# STM32F429_minimum_system.net
KiCad netlist of a schematic drawn in Altium Designer
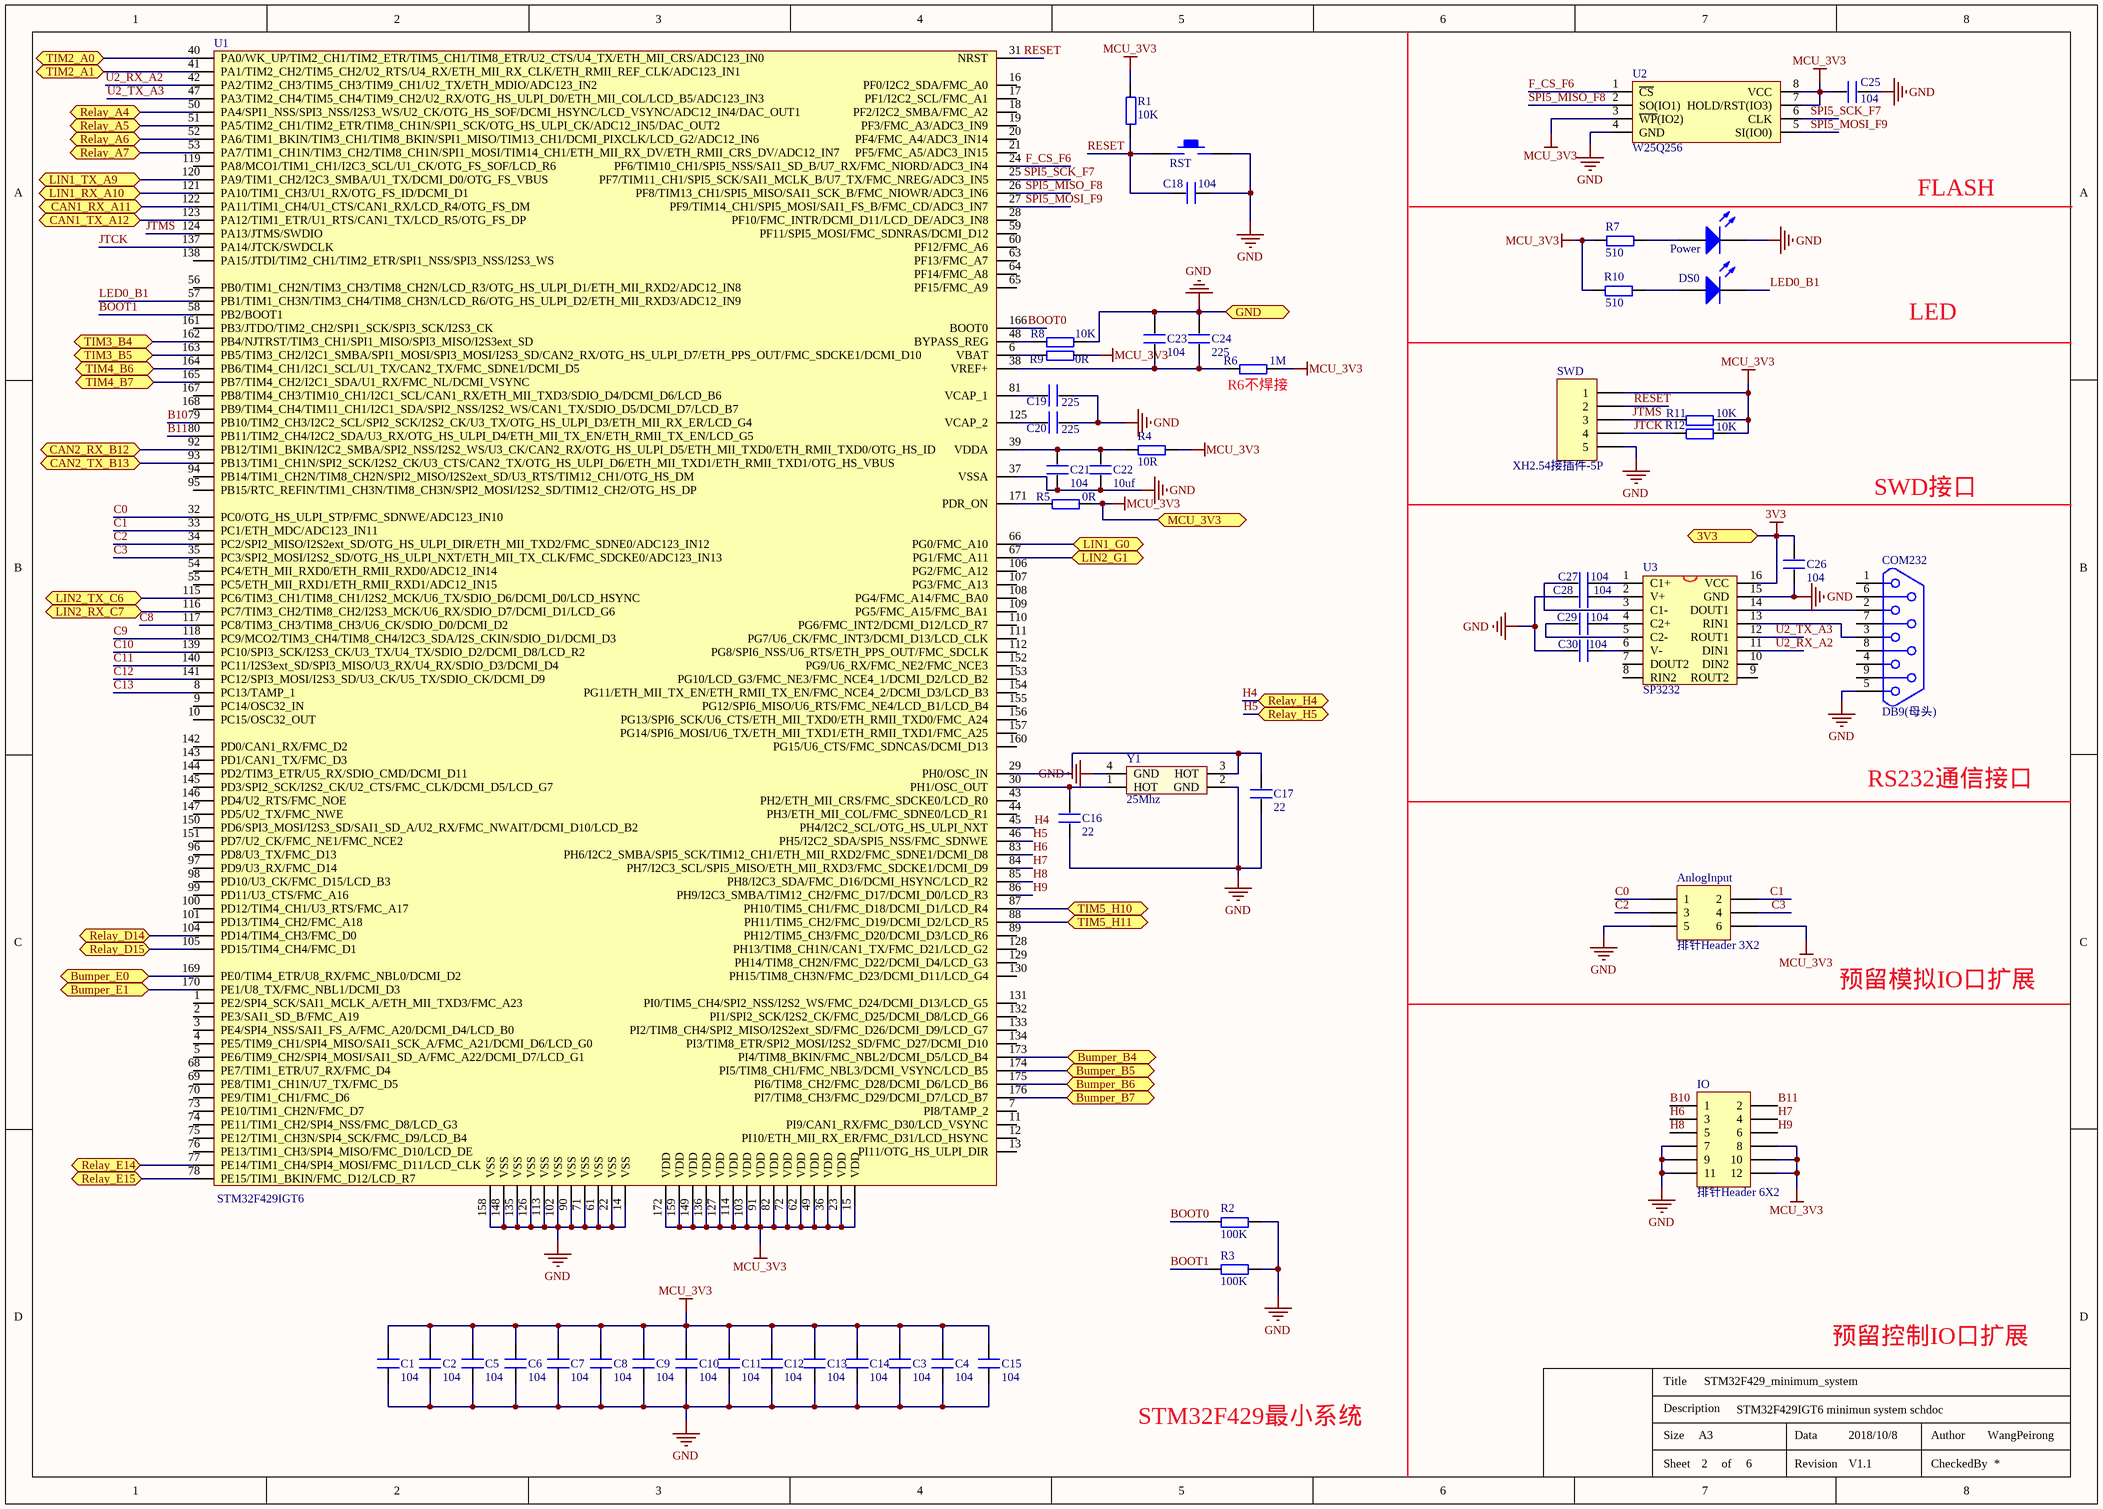
[diagram p0: STM32F429_minimum_system.SchDoc]

(export (version "E")
  (design (tool "Eeschema 10.0.6"))
  (components
    (comp (ref "AnlogInput")
      (value "排针Header 3X2")
      (footprint "F-HEADER-2*3-2.54MM")
      (description "Header, 3-Pin, Dual row")
      (fields (field (name "PUBLISHER") "Altium Limited"))
      (libsource (lib "接插件集成库") (part "Header 3X2"))
    )
    (comp (ref "C1") (value "104") (footprint "0603P") (libsource (lib "阿波罗STM32F4&F7底板封装库") (part "C")))
    (comp (ref "C2") (value "104") (footprint "0603P") (libsource (lib "阿波罗STM32F4&F7底板封装库") (part "C")))
    (comp (ref "C3") (value "104") (footprint "0603P") (libsource (lib "阿波罗STM32F4&F7底板封装库") (part "C")))
    (comp (ref "C4") (value "104") (footprint "0603P") (libsource (lib "阿波罗STM32F4&F7底板封装库") (part "C")))
    (comp (ref "C5") (value "104") (footprint "0603P") (libsource (lib "阿波罗STM32F4&F7底板封装库") (part "C")))
    (comp (ref "C6") (value "104") (footprint "0603P") (libsource (lib "阿波罗STM32F4&F7底板封装库") (part "C")))
    (comp (ref "C7") (value "104") (footprint "0603P") (libsource (lib "阿波罗STM32F4&F7底板封装库") (part "C")))
    (comp (ref "C8") (value "104") (footprint "0603P") (libsource (lib "阿波罗STM32F4&F7底板封装库") (part "C")))
    (comp (ref "C9") (value "104") (footprint "0603P") (libsource (lib "阿波罗STM32F4&F7底板封装库") (part "C")))
    (comp (ref "C10") (value "104") (footprint "0603P") (libsource (lib "阿波罗STM32F4&F7底板封装库") (part "C")))
    (comp (ref "C11") (value "104") (footprint "0603P") (libsource (lib "阿波罗STM32F4&F7底板封装库") (part "C")))
    (comp (ref "C12") (value "104") (footprint "0603P") (libsource (lib "阿波罗STM32F4&F7底板封装库") (part "C")))
    (comp (ref "C13") (value "104") (footprint "0603P") (libsource (lib "阿波罗STM32F4&F7底板封装库") (part "C")))
    (comp (ref "C14") (value "104") (footprint "0603P") (libsource (lib "阿波罗STM32F4&F7底板封装库") (part "C")))
    (comp (ref "C15") (value "104") (footprint "0603P") (libsource (lib "阿波罗STM32F4&F7底板封装库") (part "C")))
    (comp (ref "C16") (value "22") (footprint "0603P") (libsource (lib "阿波罗STM32F4&F7底板封装库") (part "C")))
    (comp (ref "C17") (value "22") (footprint "0603P") (libsource (lib "阿波罗STM32F4&F7底板封装库") (part "C")))
    (comp (ref "C18") (value "104") (footprint "0603P") (libsource (lib "阿波罗STM32F4&F7底板封装库") (part "C")))
    (comp (ref "C19") (value "225") (footprint "0603P") (libsource (lib "阿波罗STM32F4&F7底板封装库") (part "C")))
    (comp (ref "C20") (value "225") (footprint "0603P") (libsource (lib "阿波罗STM32F4&F7底板封装库") (part "C")))
    (comp (ref "C21") (value "104") (footprint "0603P") (libsource (lib "阿波罗STM32F4&F7底板封装库") (part "C")))
    (comp (ref "C22") (value "10uf") (footprint "0603P") (libsource (lib "阿波罗STM32F4&F7底板封装库") (part "C")))
    (comp (ref "C23") (value "104") (footprint "0603P") (libsource (lib "阿波罗STM32F4&F7底板封装库") (part "C")))
    (comp (ref "C24") (value "225") (footprint "0603P") (libsource (lib "阿波罗STM32F4&F7底板封装库") (part "C")))
    (comp (ref "C25") (value "104") (footprint "0603P") (libsource (lib "阿波罗STM32F4&F7底板封装库") (part "C")))
    (comp (ref "C26") (value "104") (footprint "0603P") (libsource (lib "STM32F767核心板封装库") (part "C")))
    (comp (ref "C27") (value "104") (footprint "0603P") (libsource (lib "STM32F767核心板封装库") (part "C")))
    (comp (ref "C28") (value "104") (footprint "0603P") (libsource (lib "STM32F767核心板封装库") (part "C")))
    (comp (ref "C29") (value "104") (footprint "0603P") (libsource (lib "STM32F767核心板封装库") (part "C")))
    (comp (ref "C30") (value "104") (footprint "0603P") (libsource (lib "STM32F767核心板封装库") (part "C")))
    (comp (ref "COM232")
      (value "DB9(母头)")
      (footprint "DB9")
      (libsource (lib "阿波罗STM32F4&F7底板封装库") (part "DB9"))
    )
    (comp (ref "DS0")
      (value "LED绿色")
      (footprint "SMDLED")
      (description "Typical RED, GREEN, YELLOW, AMBER GaAs LED")
      (fields (field (name "PUBLISHER") "Altium Limited"))
      (libsource (lib "阿波罗STM32F4&F7底板封装库") (part "LED2"))
    )
    (comp (ref "IO")
      (value "排针Header 6X2")
      (footprint "F-HEADER-2*6-2.54MM")
      (description "Header, 6-Pin, Dual row")
      (fields (field (name "PUBLISHER") "Altium Limited"))
      (libsource (lib "接插件集成库") (part "Header 6X2"))
    )
    (comp (ref "Power")
      (value "LED红色")
      (footprint "SMDLED")
      (description "Typical RED, GREEN, YELLOW, AMBER GaAs LED")
      (fields (field (name "PUBLISHER") "Altium Limited"))
      (libsource (lib "阿波罗STM32F4&F7底板封装库") (part "LED2"))
    )
    (comp (ref "R1") (value "10K") (footprint "0603P") (libsource (lib "STM32F429核心板封装库") (part "R")))
    (comp (ref "R2") (value "100K") (footprint "0603P") (libsource (lib "STM32F429核心板封装库") (part "R")))
    (comp (ref "R3") (value "100K") (footprint "0603P") (libsource (lib "STM32F429核心板封装库") (part "R")))
    (comp (ref "R4") (value "10R") (footprint "0603P") (libsource (lib "STM32F429核心板封装库") (part "R")))
    (comp (ref "R5") (value "0R") (footprint "0603P") (libsource (lib "STM32F429核心板封装库") (part "R")))
    (comp (ref "R6") (value "1M") (footprint "0603P") (libsource (lib "STM32F429核心板封装库") (part "R")))
    (comp (ref "R7") (value "510") (footprint "0603P") (libsource (lib "STM32F429核心板封装库") (part "R")))
    (comp (ref "R8") (value "10K") (footprint "0603P") (libsource (lib "STM32F429核心板封装库") (part "R")))
    (comp (ref "R9") (value "0R") (footprint "0603P") (libsource (lib "STM32F429核心板封装库") (part "R")))
    (comp (ref "R10") (value "510") (footprint "0603P") (libsource (lib "STM32F429核心板封装库") (part "R")))
    (comp (ref "R11") (value "10K") (footprint "0603P") (libsource (lib "STM32F429核心板封装库") (part "R")))
    (comp (ref "R12") (value "10K") (footprint "0603P") (libsource (lib "STM32F429核心板封装库") (part "R")))
    (comp (ref "RST")
      (value "KEY_M")
      (footprint "KEY_SOP3625")
      (libsource (lib "STM32F429核心板封装库") (part "KEY_M"))
    )
    (comp (ref "SWD")
      (value "XH2.54接插件-5P")
      (footprint "F-HEADER-5-2.54MM")
      (description "Header, 5-Pin")
      (fields (field (name "PUBLISHER") "Altium Limited"))
      (libsource (lib "接插件集成库") (part "Header 5"))
    )
    (comp (ref "U1")
      (value "STM32F429IGT6")
      (footprint "LQFP176")
      (libsource (lib "STM32F429核心板封装库") (part "STM32F429IGT6"))
    )
    (comp (ref "U2")
      (value "W25Q256")
      (footprint "WSON8")
      (description "W25Q128")
      (libsource (lib "STM32F429核心板封装库") (part "W25Q128"))
    )
    (comp (ref "U3")
      (value "SP3232")
      (footprint "SOP16M")
      (libsource (lib "阿波罗STM32F4&F7底板封装库") (part "MAX3232"))
    )
    (comp (ref "Y1")
      (value "25Mhz")
      (footprint "XTAL3225")
      (description "3225贴片无源晶振")
      (libsource (lib "STM32F429核心板封装库") (part "XTAL_3225"))
    )
  )
  (nets
    (net (code "1") (name "/B10") (class "Default")
      (node (ref "IO") (pin "1") (pinfunction "1_1") (pintype "passive"))
      (node (ref "U1") (pin "79") (pinfunction "PB10/TIM2_CH3/I2C2_SCL/SPI2_SCK/I2S2_CK/U3_TX/OTG_HS_ULPI_D3/ETH_MII_RX_ER/LCD_G4_79") (pintype "passive"))
    )
    (net (code "2") (name "/B11") (class "Default")
      (node (ref "IO") (pin "2") (pinfunction "2_2") (pintype "passive"))
      (node (ref "U1") (pin "80") (pinfunction "PB11/TIM2_CH4/I2C2_SDA/U3_RX/OTG_HS_ULPI_D4/ETH_MII_TX_EN/ETH_RMII_TX_EN/LCD_G5_80") (pintype "passive"))
    )
    (net (code "3") (name "/BOOT0") (class "Default")
      (node (ref "R2") (pin "1") (pintype "passive"))
      (node (ref "U1") (pin "166") (pinfunction "BOOT0_166") (pintype "passive"))
    )
    (net (code "4") (name "/BOOT1") (class "Default")
      (node (ref "R3") (pin "1") (pintype "passive"))
      (node (ref "U1") (pin "58") (pinfunction "PB2/BOOT1_58") (pintype "passive"))
    )
    (net (code "5") (name "/Bumper_B4") (class "Default")
      (node (ref "U1") (pin "173") (pinfunction "PI4/TIM8_BKIN/FMC_NBL2/DCMI_D5/LCD_B4_173") (pintype "passive"))
    )
    (net (code "6") (name "/Bumper_B5") (class "Default")
      (node (ref "U1") (pin "174") (pinfunction "PI5/TIM8_CH1/FMC_NBL3/DCMI_VSYNC/LCD_B5_174") (pintype "passive"))
    )
    (net (code "7") (name "/Bumper_B6") (class "Default")
      (node (ref "U1") (pin "175") (pinfunction "PI6/TIM8_CH2/FMC_D28/DCMI_D6/LCD_B6_175") (pintype "passive"))
    )
    (net (code "8") (name "/Bumper_B7") (class "Default")
      (node (ref "U1") (pin "176") (pinfunction "PI7/TIM8_CH3/FMC_D29/DCMI_D7/LCD_B7_176") (pintype "passive"))
    )
    (net (code "9") (name "/Bumper_E0") (class "Default")
      (node (ref "U1") (pin "169") (pinfunction "PE0/TIM4_ETR/U8_RX/FMC_NBL0/DCMI_D2_169") (pintype "passive"))
    )
    (net (code "10") (name "/Bumper_E1") (class "Default")
      (node (ref "U1") (pin "170") (pinfunction "PE1/U8_TX/FMC_NBL1/DCMI_D3_170") (pintype "passive"))
    )
    (net (code "11") (name "/C0") (class "Default")
      (node (ref "AnlogInput") (pin "1") (pinfunction "1_1") (pintype "passive"))
      (node (ref "U1") (pin "32") (pinfunction "PC0/OTG_HS_ULPI_STP/FMC_SDNWE/ADC123_IN10_32") (pintype "passive"))
    )
    (net (code "12") (name "/C1") (class "Default")
      (node (ref "AnlogInput") (pin "2") (pinfunction "2_2") (pintype "passive"))
      (node (ref "U1") (pin "33") (pinfunction "PC1/ETH_MDC/ADC123_IN11_33") (pintype "passive"))
    )
    (net (code "13") (name "/C2") (class "Default")
      (node (ref "AnlogInput") (pin "3") (pinfunction "3_3") (pintype "passive"))
      (node (ref "U1") (pin "34") (pinfunction "PC2/SPI2_MISO/I2S2ext_SD/OTG_HS_ULPI_DIR/ETH_MII_TXD2/FMC_SDNE0/ADC123_IN12_34") (pintype "passive"))
    )
    (net (code "14") (name "/C3") (class "Default")
      (node (ref "AnlogInput") (pin "4") (pinfunction "4_4") (pintype "passive"))
      (node (ref "U1") (pin "35") (pinfunction "PC3/SPI2_MOSI/I2S2_SD/OTG_HS_ULPI_NXT/ETH_MII_TX_CLK/FMC_SDCKE0/ADC123_IN13_35") (pintype "passive"))
    )
    (net (code "15") (name "/C8") (class "Default")
      (node (ref "U1") (pin "117") (pinfunction "PC8/TIM3_CH3/TIM8_CH3/U6_CK/SDIO_D0/DCMI_D2_117") (pintype "passive"))
    )
    (net (code "16") (name "/C9") (class "Default")
      (node (ref "U1") (pin "118") (pinfunction "PC9/MCO2/TIM3_CH4/TIM8_CH4/I2C3_SDA/I2S_CKIN/SDIO_D1/DCMI_D3_118") (pintype "passive"))
    )
    (net (code "17") (name "/C10") (class "Default")
      (node (ref "U1") (pin "139") (pinfunction "PC10/SPI3_SCK/I2S3_CK/U3_TX/U4_TX/SDIO_D2/DCMI_D8/LCD_R2_139") (pintype "passive"))
    )
    (net (code "18") (name "/C11") (class "Default")
      (node (ref "U1") (pin "140") (pinfunction "PC11/I2S3ext_SD/SPI3_MISO/U3_RX/U4_RX/SDIO_D3/DCMI_D4_140") (pintype "passive"))
    )
    (net (code "19") (name "/C12") (class "Default")
      (node (ref "U1") (pin "141") (pinfunction "PC12/SPI3_MOSI/I2S3_SD/U3_CK/U5_TX/SDIO_CK/DCMI_D9_141") (pintype "passive"))
    )
    (net (code "20") (name "/C13") (class "Default")
      (node (ref "U1") (pin "8") (pinfunction "PC13/TAMP_1_8") (pintype "passive"))
    )
    (net (code "21") (name "/CAN1_RX_A11") (class "Default")
      (node (ref "U1") (pin "122") (pinfunction "PA11/TIM1_CH4/U1_CTS/CAN1_RX/LCD_R4/OTG_FS_DM_122") (pintype "passive"))
    )
    (net (code "22") (name "/CAN1_TX_A12") (class "Default")
      (node (ref "U1") (pin "123") (pinfunction "PA12/TIM1_ETR/U1_RTS/CAN1_TX/LCD_R5/OTG_FS_DP_123") (pintype "passive"))
    )
    (net (code "23") (name "/CAN2_RX_B12") (class "Default")
      (node (ref "U1") (pin "92") (pinfunction "PB12/TIM1_BKIN/I2C2_SMBA/SPI2_NSS/I2S2_WS/U3_CK/CAN2_RX/OTG_HS_ULPI_D5/ETH_MII_TXD0/ETH_RMII_TXD0/OTG_HS_ID_92") (pintype "passive"))
    )
    (net (code "24") (name "/CAN2_TX_B13") (class "Default")
      (node (ref "U1") (pin "93") (pinfunction "PB13/TIM1_CH1N/SPI2_SCK/I2S2_CK/U3_CTS/CAN2_TX/OTG_HS_ULPI_D6/ETH_MII_TXD1/ETH_RMII_TXD1/OTG_HS_VBUS_93") (pintype "passive"))
    )
    (net (code "25") (name "/F_CS_F6") (class "Default")
      (node (ref "U1") (pin "24") (pinfunction "PF6/TIM10_CH1/SPI5_NSS/SAI1_SD_B/U7_RX/FMC_NIORD/ADC3_IN4_24") (pintype "passive"))
      (node (ref "U2") (pin "1") (pinfunction "~{CS}_1") (pintype "passive"))
    )
    (net (code "26") (name "/H4") (class "Default")
      (node (ref "U1") (pin "45") (pinfunction "PH4/I2C2_SCL/OTG_HS_ULPI_NXT_45") (pintype "passive"))
    )
    (net (code "27") (name "/H5") (class "Default")
      (node (ref "U1") (pin "46") (pinfunction "PH5/I2C2_SDA/SPI5_NSS/FMC_SDNWE_46") (pintype "passive"))
    )
    (net (code "28") (name "/H6") (class "Default")
      (node (ref "IO") (pin "3") (pinfunction "3_3") (pintype "passive"))
      (node (ref "U1") (pin "83") (pinfunction "PH6/I2C2_SMBA/SPI5_SCK/TIM12_CH1/ETH_MII_RXD2/FMC_SDNE1/DCMI_D8_83") (pintype "passive"))
    )
    (net (code "29") (name "/H7") (class "Default")
      (node (ref "IO") (pin "4") (pinfunction "4_4") (pintype "passive"))
      (node (ref "U1") (pin "84") (pinfunction "PH7/I2C3_SCL/SPI5_MISO/ETH_MII_RXD3/FMC_SDCKE1/DCMI_D9_84") (pintype "passive"))
    )
    (net (code "30") (name "/H8") (class "Default")
      (node (ref "IO") (pin "5") (pinfunction "5_5") (pintype "passive"))
      (node (ref "U1") (pin "85") (pinfunction "PH8/I2C3_SDA/FMC_D16/DCMI_HSYNC/LCD_R2_85") (pintype "passive"))
    )
    (net (code "31") (name "/H9") (class "Default")
      (node (ref "IO") (pin "6") (pinfunction "6_6") (pintype "passive"))
      (node (ref "U1") (pin "86") (pinfunction "PH9/I2C3_SMBA/TIM12_CH2/FMC_D17/DCMI_D0/LCD_R3_86") (pintype "passive"))
    )
    (net (code "32") (name "/JTCK") (class "Default")
      (node (ref "R12") (pin "1") (pintype "passive"))
      (node (ref "SWD") (pin "4") (pinfunction "4_4") (pintype "passive"))
      (node (ref "U1") (pin "137") (pinfunction "PA14/JTCK/SWDCLK_137") (pintype "passive"))
    )
    (net (code "33") (name "/JTMS") (class "Default")
      (node (ref "R11") (pin "1") (pintype "passive"))
      (node (ref "SWD") (pin "3") (pinfunction "3_3") (pintype "passive"))
      (node (ref "U1") (pin "124") (pinfunction "PA13/JTMS/SWDIO_124") (pintype "passive"))
    )
    (net (code "34") (name "/LED0_B1") (class "Default")
      (node (ref "DS0") (pin "2") (pinfunction "K_2") (pintype "passive"))
      (node (ref "U1") (pin "57") (pinfunction "PB1/TIM1_CH3N/TIM3_CH4/TIM8_CH3N/LCD_R6/OTG_HS_ULPI_D2/ETH_MII_RXD3/ADC12_IN9_57") (pintype "passive"))
    )
    (net (code "35") (name "/LIN1_G0") (class "Default")
      (node (ref "U1") (pin "66") (pinfunction "PG0/FMC_A10_66") (pintype "passive"))
    )
    (net (code "36") (name "/LIN1_RX_A10") (class "Default")
      (node (ref "U1") (pin "121") (pinfunction "PA10/TIM1_CH3/U1_RX/OTG_FS_ID/DCMI_D1_121") (pintype "passive"))
    )
    (net (code "37") (name "/LIN1_TX_A9") (class "Default")
      (node (ref "U1") (pin "120") (pinfunction "PA9/TIM1_CH2/I2C3_SMBA/U1_TX/DCMI_D0/OTG_FS_VBUS_120") (pintype "passive"))
    )
    (net (code "38") (name "/LIN2_G1") (class "Default")
      (node (ref "U1") (pin "67") (pinfunction "PG1/FMC_A11_67") (pintype "passive"))
    )
    (net (code "39") (name "/LIN2_RX_C7") (class "Default")
      (node (ref "U1") (pin "116") (pinfunction "PC7/TIM3_CH2/TIM8_CH2/I2S3_MCK/U6_RX/SDIO_D7/DCMI_D1/LCD_G6_116") (pintype "passive"))
    )
    (net (code "40") (name "/LIN2_TX_C6") (class "Default")
      (node (ref "U1") (pin "115") (pinfunction "PC6/TIM3_CH1/TIM8_CH1/I2S2_MCK/U6_TX/SDIO_D6/DCMI_D0/LCD_HSYNC_115") (pintype "passive"))
    )
    (net (code "41") (name "/RESET") (class "Default")
      (node (ref "C18") (pin "1") (pintype "passive"))
      (node (ref "R1") (pin "1") (pintype "passive"))
      (node (ref "RST") (pin "1") (pinfunction "1_1") (pintype "passive"))
      (node (ref "SWD") (pin "2") (pinfunction "2_2") (pintype "passive"))
      (node (ref "U1") (pin "31") (pinfunction "NRST_31") (pintype "passive"))
    )
    (net (code "42") (name "/Relay_A4") (class "Default")
      (node (ref "U1") (pin "50") (pinfunction "PA4/SPI1_NSS/SPI3_NSS/I2S3_WS/U2_CK/OTG_HS_SOF/DCMI_HSYNC/LCD_VSYNC/ADC12_IN4/DAC_OUT1_50") (pintype "passive"))
    )
    (net (code "43") (name "/Relay_A5") (class "Default")
      (node (ref "U1") (pin "51") (pinfunction "PA5/TIM2_CH1/TIM2_ETR/TIM8_CH1N/SPI1_SCK/OTG_HS_ULPI_CK/ADC12_IN5/DAC_OUT2_51") (pintype "passive"))
    )
    (net (code "44") (name "/Relay_A6") (class "Default")
      (node (ref "U1") (pin "52") (pinfunction "PA6/TIM1_BKIN/TIM3_CH1/TIM8_BKIN/SPI1_MISO/TIM13_CH1/DCMI_PIXCLK/LCD_G2/ADC12_IN6_52") (pintype "passive"))
    )
    (net (code "45") (name "/Relay_A7") (class "Default")
      (node (ref "U1") (pin "53") (pinfunction "PA7/TIM1_CH1N/TIM3_CH2/TIM8_CH1N/SPI1_MOSI/TIM14_CH1/ETH_MII_RX_DV/ETH_RMII_CRS_DV/ADC12_IN7_53") (pintype "passive"))
    )
    (net (code "46") (name "/Relay_D14") (class "Default")
      (node (ref "U1") (pin "104") (pinfunction "PD14/TIM4_CH3/FMC_D0_104") (pintype "passive"))
    )
    (net (code "47") (name "/Relay_D15") (class "Default")
      (node (ref "U1") (pin "105") (pinfunction "PD15/TIM4_CH4/FMC_D1_105") (pintype "passive"))
    )
    (net (code "48") (name "/Relay_E14") (class "Default")
      (node (ref "U1") (pin "77") (pinfunction "PE14/TIM1_CH4/SPI4_MOSI/FMC_D11/LCD_CLK_77") (pintype "passive"))
    )
    (net (code "49") (name "/Relay_E15") (class "Default")
      (node (ref "U1") (pin "78") (pinfunction "PE15/TIM1_BKIN/FMC_D12/LCD_R7_78") (pintype "passive"))
    )
    (net (code "50") (name "/SPI5_MISO_F8") (class "Default")
      (node (ref "U1") (pin "26") (pinfunction "PF8/TIM13_CH1/SPI5_MISO/SAI1_SCK_B/FMC_NIOWR/ADC3_IN6_26") (pintype "passive"))
      (node (ref "U2") (pin "2") (pinfunction "SO(IO1)_2") (pintype "passive"))
    )
    (net (code "51") (name "/SPI5_MOSI_F9") (class "Default")
      (node (ref "U1") (pin "27") (pinfunction "PF9/TIM14_CH1/SPI5_MOSI/SAI1_FS_B/FMC_CD/ADC3_IN7_27") (pintype "passive"))
      (node (ref "U2") (pin "5") (pinfunction "SI(IO0)_5") (pintype "power_in"))
    )
    (net (code "52") (name "/SPI5_SCK_F7") (class "Default")
      (node (ref "U1") (pin "25") (pinfunction "PF7/TIM11_CH1/SPI5_SCK/SAI1_MCLK_B/U7_TX/FMC_NREG/ADC3_IN5_25") (pintype "passive"))
      (node (ref "U2") (pin "6") (pinfunction "CLK_6") (pintype "passive"))
    )
    (net (code "53") (name "/TIM2_A0") (class "Default")
      (node (ref "U1") (pin "40") (pinfunction "PA0/WK_UP/TIM2_CH1/TIM2_ETR/TIM5_CH1/TIM8_ETR/U2_CTS/U4_TX/ETH_MII_CRS/ADC123_IN0_40") (pintype "passive"))
    )
    (net (code "54") (name "/TIM2_A1") (class "Default")
      (node (ref "U1") (pin "41") (pinfunction "PA1/TIM2_CH2/TIM5_CH2/U2_RTS/U4_RX/ETH_MII_RX_CLK/ETH_RMII_REF_CLK/ADC123_IN1_41") (pintype "passive"))
    )
    (net (code "55") (name "/TIM3_B4") (class "Default")
      (node (ref "U1") (pin "162") (pinfunction "PB4/NJTRST/TIM3_CH1/SPI1_MISO/SPI3_MISO/I2S3ext_SD_162") (pintype "passive"))
    )
    (net (code "56") (name "/TIM3_B5") (class "Default")
      (node (ref "U1") (pin "163") (pinfunction "PB5/TIM3_CH2/I2C1_SMBA/SPI1_MOSI/SPI3_MOSI/I2S3_SD/CAN2_RX/OTG_HS_ULPI_D7/ETH_PPS_OUT/FMC_SDCKE1/DCMI_D10_163") (pintype "passive"))
    )
    (net (code "57") (name "/TIM4_B6") (class "Default")
      (node (ref "U1") (pin "164") (pinfunction "PB6/TIM4_CH1/I2C1_SCL/U1_TX/CAN2_TX/FMC_SDNE1/DCMI_D5_164") (pintype "passive"))
    )
    (net (code "58") (name "/TIM4_B7") (class "Default")
      (node (ref "U1") (pin "165") (pinfunction "PB7/TIM4_CH2/I2C1_SDA/U1_RX/FMC_NL/DCMI_VSYNC_165") (pintype "passive"))
    )
    (net (code "59") (name "/TIM5_H10") (class "Default")
      (node (ref "U1") (pin "87") (pinfunction "PH10/TIM5_CH1/FMC_D18/DCMI_D1/LCD_R4_87") (pintype "passive"))
    )
    (net (code "60") (name "/TIM5_H11") (class "Default")
      (node (ref "U1") (pin "88") (pinfunction "PH11/TIM5_CH2/FMC_D19/DCMI_D2/LCD_R5_88") (pintype "passive"))
    )
    (net (code "61") (name "/U2_RX_A2") (class "Default")
      (node (ref "U1") (pin "42") (pinfunction "PA2/TIM2_CH3/TIM5_CH3/TIM9_CH1/U2_TX/ETH_MDIO/ADC123_IN2_42") (pintype "passive"))
      (node (ref "U3") (pin "11") (pinfunction "DIN1_11") (pintype "passive"))
    )
    (net (code "62") (name "/U2_TX_A3") (class "Default")
      (node (ref "U1") (pin "47") (pinfunction "PA3/TIM2_CH4/TIM5_CH4/TIM9_CH2/U2_RX/OTG_HS_ULPI_D0/ETH_MII_COL/LCD_B5/ADC123_IN3_47") (pintype "passive"))
      (node (ref "U3") (pin "12") (pinfunction "ROUT1_12") (pintype "passive"))
    )
    (net (code "63") (name "3V3") (class "Default")
      (node (ref "C26") (pin "2") (pintype "passive"))
      (node (ref "U3") (pin "16") (pinfunction "VCC_16") (pintype "passive"))
    )
    (net (code "64") (name "GND") (class "Default")
      (node (ref "AnlogInput") (pin "5") (pinfunction "5_5") (pintype "passive"))
      (node (ref "C1") (pin "1") (pintype "passive"))
      (node (ref "C10") (pin "1") (pintype "passive"))
      (node (ref "C11") (pin "1") (pintype "passive"))
      (node (ref "C12") (pin "1") (pintype "passive"))
      (node (ref "C13") (pin "1") (pintype "passive"))
      (node (ref "C14") (pin "1") (pintype "passive"))
      (node (ref "C15") (pin "1") (pintype "passive"))
      (node (ref "C16") (pin "2") (pintype "passive"))
      (node (ref "C17") (pin "2") (pintype "passive"))
      (node (ref "C18") (pin "2") (pintype "passive"))
      (node (ref "C19") (pin "2") (pintype "passive"))
      (node (ref "C2") (pin "1") (pintype "passive"))
      (node (ref "C20") (pin "2") (pintype "passive"))
      (node (ref "C21") (pin "1") (pintype "passive"))
      (node (ref "C22") (pin "1") (pintype "passive"))
      (node (ref "C23") (pin "2") (pintype "passive"))
      (node (ref "C24") (pin "2") (pintype "passive"))
      (node (ref "C25") (pin "2") (pintype "passive"))
      (node (ref "C26") (pin "1") (pintype "passive"))
      (node (ref "C28") (pin "2") (pintype "passive"))
      (node (ref "C3") (pin "1") (pintype "passive"))
      (node (ref "C30") (pin "2") (pintype "passive"))
      (node (ref "C4") (pin "1") (pintype "passive"))
      (node (ref "C5") (pin "1") (pintype "passive"))
      (node (ref "C6") (pin "1") (pintype "passive"))
      (node (ref "C7") (pin "1") (pintype "passive"))
      (node (ref "C8") (pin "1") (pintype "passive"))
      (node (ref "C9") (pin "1") (pintype "passive"))
      (node (ref "COM232") (pin "5") (pinfunction "5_5") (pintype "passive"))
      (node (ref "IO") (pin "11") (pinfunction "11_11") (pintype "passive"))
      (node (ref "IO") (pin "7") (pinfunction "7_7") (pintype "passive"))
      (node (ref "IO") (pin "9") (pinfunction "9_9") (pintype "passive"))
      (node (ref "Power") (pin "2") (pinfunction "K_2") (pintype "passive"))
      (node (ref "R2") (pin "2") (pintype "passive"))
      (node (ref "R3") (pin "2") (pintype "passive"))
      (node (ref "R8") (pin "2") (pintype "passive"))
      (node (ref "RST") (pin "2") (pinfunction "2_2") (pintype "passive"))
      (node (ref "SWD") (pin "5") (pinfunction "5_5") (pintype "passive"))
      (node (ref "U1") (pin "102") (pinfunction "VSS_102") (pintype "passive"))
      (node (ref "U1") (pin "113") (pinfunction "VSS_113") (pintype "passive"))
      (node (ref "U1") (pin "126") (pinfunction "VSS_126") (pintype "passive"))
      (node (ref "U1") (pin "135") (pinfunction "VSS_135") (pintype "passive"))
      (node (ref "U1") (pin "14") (pinfunction "VSS_14") (pintype "passive"))
      (node (ref "U1") (pin "148") (pinfunction "VSS_148") (pintype "passive"))
      (node (ref "U1") (pin "158") (pinfunction "VSS_158") (pintype "passive"))
      (node (ref "U1") (pin "22") (pinfunction "VSS_22") (pintype "passive"))
      (node (ref "U1") (pin "37") (pinfunction "VSSA_37") (pintype "passive"))
      (node (ref "U1") (pin "61") (pinfunction "VSS_61") (pintype "passive"))
      (node (ref "U1") (pin "71") (pinfunction "VSS_71") (pintype "passive"))
      (node (ref "U1") (pin "90") (pinfunction "VSS_90") (pintype "passive"))
      (node (ref "U2") (pin "4") (pinfunction "GND_4") (pintype "passive"))
      (node (ref "U3") (pin "15") (pinfunction "GND_15") (pintype "passive"))
      (node (ref "Y1") (pin "2") (pinfunction "GND_2") (pintype "passive"))
      (node (ref "Y1") (pin "4") (pinfunction "GND_4") (pintype "passive"))
    )
    (net (code "65") (name "MCU_3V3") (class "Default")
      (node (ref "AnlogInput") (pin "6") (pinfunction "6_6") (pintype "passive"))
      (node (ref "C1") (pin "2") (pintype "passive"))
      (node (ref "C10") (pin "2") (pintype "passive"))
      (node (ref "C11") (pin "2") (pintype "passive"))
      (node (ref "C12") (pin "2") (pintype "passive"))
      (node (ref "C13") (pin "2") (pintype "passive"))
      (node (ref "C14") (pin "2") (pintype "passive"))
      (node (ref "C15") (pin "2") (pintype "passive"))
      (node (ref "C2") (pin "2") (pintype "passive"))
      (node (ref "C25") (pin "1") (pintype "passive"))
      (node (ref "C3") (pin "2") (pintype "passive"))
      (node (ref "C4") (pin "2") (pintype "passive"))
      (node (ref "C5") (pin "2") (pintype "passive"))
      (node (ref "C6") (pin "2") (pintype "passive"))
      (node (ref "C7") (pin "2") (pintype "passive"))
      (node (ref "C8") (pin "2") (pintype "passive"))
      (node (ref "C9") (pin "2") (pintype "passive"))
      (node (ref "IO") (pin "10") (pinfunction "10_10") (pintype "passive"))
      (node (ref "IO") (pin "12") (pinfunction "12_12") (pintype "passive"))
      (node (ref "IO") (pin "8") (pinfunction "8_8") (pintype "passive"))
      (node (ref "R1") (pin "2") (pintype "passive"))
      (node (ref "R10") (pin "1") (pintype "passive"))
      (node (ref "R11") (pin "2") (pintype "passive"))
      (node (ref "R12") (pin "2") (pintype "passive"))
      (node (ref "R4") (pin "2") (pintype "passive"))
      (node (ref "R5") (pin "2") (pintype "passive"))
      (node (ref "R6") (pin "2") (pintype "passive"))
      (node (ref "R7") (pin "1") (pintype "passive"))
      (node (ref "R9") (pin "2") (pintype "passive"))
      (node (ref "SWD") (pin "1") (pinfunction "1_1") (pintype "passive"))
      (node (ref "U1") (pin "103") (pinfunction "VDD_103") (pintype "passive"))
      (node (ref "U1") (pin "114") (pinfunction "VDD_114") (pintype "passive"))
      (node (ref "U1") (pin "127") (pinfunction "VDD_127") (pintype "passive"))
      (node (ref "U1") (pin "136") (pinfunction "VDD_136") (pintype "passive"))
      (node (ref "U1") (pin "149") (pinfunction "VDD_149") (pintype "passive"))
      (node (ref "U1") (pin "15") (pinfunction "VDD_15") (pintype "passive"))
      (node (ref "U1") (pin "159") (pinfunction "VDD_159") (pintype "passive"))
      (node (ref "U1") (pin "172") (pinfunction "VDD_172") (pintype "passive"))
      (node (ref "U1") (pin "23") (pinfunction "VDD_23") (pintype "passive"))
      (node (ref "U1") (pin "36") (pinfunction "VDD_36") (pintype "passive"))
      (node (ref "U1") (pin "49") (pinfunction "VDD_49") (pintype "passive"))
      (node (ref "U1") (pin "62") (pinfunction "VDD_62") (pintype "passive"))
      (node (ref "U1") (pin "72") (pinfunction "VDD_72") (pintype "passive"))
      (node (ref "U1") (pin "82") (pinfunction "VDD_82") (pintype "passive"))
      (node (ref "U1") (pin "91") (pinfunction "VDD_91") (pintype "passive"))
      (node (ref "U2") (pin "3") (pinfunction "~{WP}(IO2)_3") (pintype "passive"))
      (node (ref "U2") (pin "7") (pinfunction "HOLD/RST(IO3)_7") (pintype "power_in"))
      (node (ref "U2") (pin "8") (pinfunction "VCC_8") (pintype "passive"))
    )
    (net (code "66") (name "Net-(DS0-A)") (class "Default")
      (node (ref "DS0") (pin "1") (pinfunction "A_1") (pintype "passive"))
      (node (ref "R10") (pin "2") (pintype "passive"))
    )
    (net (code "67") (name "Net-(Power-A)") (class "Default")
      (node (ref "Power") (pin "1") (pinfunction "A_1") (pintype "passive"))
      (node (ref "R7") (pin "2") (pintype "passive"))
    )
    (net (code "68") (name "Net-(U1-BYPASS_REG)") (class "Default")
      (node (ref "R8") (pin "1") (pintype "passive"))
      (node (ref "U1") (pin "48") (pinfunction "BYPASS_REG_48") (pintype "passive"))
    )
    (net (code "69") (name "Net-(U1-PDR_ON)") (class "Default")
      (node (ref "R5") (pin "1") (pintype "passive"))
      (node (ref "U1") (pin "171") (pinfunction "PDR_ON_171") (pintype "passive"))
    )
    (net (code "70") (name "Net-(U1-PH0{slash}OSC_IN)") (class "Default")
      (node (ref "C17") (pin "1") (pintype "passive"))
      (node (ref "U1") (pin "29") (pinfunction "PH0/OSC_IN_29") (pintype "passive"))
      (node (ref "Y1") (pin "3") (pinfunction "HOT_3") (pintype "passive"))
    )
    (net (code "71") (name "Net-(U1-PH1{slash}OSC_OUT)") (class "Default")
      (node (ref "C16") (pin "1") (pintype "passive"))
      (node (ref "U1") (pin "30") (pinfunction "PH1/OSC_OUT_30") (pintype "passive"))
      (node (ref "Y1") (pin "1") (pinfunction "HOT_1") (pintype "passive"))
    )
    (net (code "72") (name "Net-(U1-VBAT)") (class "Default")
      (node (ref "R9") (pin "1") (pintype "passive"))
      (node (ref "U1") (pin "6") (pinfunction "VBAT_6") (pintype "passive"))
    )
    (net (code "73") (name "Net-(U1-VCAP_1)") (class "Default")
      (node (ref "C19") (pin "1") (pintype "passive"))
      (node (ref "U1") (pin "81") (pinfunction "VCAP_1_81") (pintype "passive"))
    )
    (net (code "74") (name "Net-(U1-VCAP_2)") (class "Default")
      (node (ref "C20") (pin "1") (pintype "passive"))
      (node (ref "U1") (pin "125") (pinfunction "VCAP_2_125") (pintype "passive"))
    )
    (net (code "75") (name "Net-(U1-VDDA)") (class "Default")
      (node (ref "C21") (pin "2") (pintype "passive"))
      (node (ref "C22") (pin "2") (pintype "passive"))
      (node (ref "R4") (pin "1") (pintype "passive"))
      (node (ref "U1") (pin "39") (pinfunction "VDDA_39") (pintype "passive"))
    )
    (net (code "76") (name "Net-(U1-VREF+)") (class "Default")
      (node (ref "C23") (pin "1") (pintype "passive"))
      (node (ref "C24") (pin "1") (pintype "passive"))
      (node (ref "R6") (pin "1") (pintype "passive"))
      (node (ref "U1") (pin "38") (pinfunction "VREF+_38") (pintype "passive"))
    )
    (net (code "77") (name "Net-(U3-C1+)") (class "Default")
      (node (ref "C27") (pin "1") (pintype "passive"))
      (node (ref "U3") (pin "1") (pinfunction "C1+_1") (pintype "passive"))
    )
    (net (code "78") (name "Net-(U3-C1-)") (class "Default")
      (node (ref "C27") (pin "2") (pintype "passive"))
      (node (ref "U3") (pin "3") (pinfunction "C1-_3") (pintype "passive"))
    )
    (net (code "79") (name "Net-(U3-C2+)") (class "Default")
      (node (ref "C29") (pin "1") (pintype "passive"))
      (node (ref "U3") (pin "4") (pinfunction "C2+_4") (pintype "passive"))
    )
    (net (code "80") (name "Net-(U3-C2-)") (class "Default")
      (node (ref "C29") (pin "2") (pintype "passive"))
      (node (ref "U3") (pin "5") (pinfunction "C2-_5") (pintype "passive"))
    )
    (net (code "81") (name "Net-(U3-DOUT1)") (class "Default")
      (node (ref "COM232") (pin "2") (pinfunction "2_2") (pintype "passive"))
      (node (ref "U3") (pin "14") (pinfunction "DOUT1_14") (pintype "passive"))
    )
    (net (code "82") (name "Net-(U3-RIN1)") (class "Default")
      (node (ref "COM232") (pin "3") (pinfunction "3_3") (pintype "passive"))
      (node (ref "U3") (pin "13") (pinfunction "RIN1_13") (pintype "passive"))
    )
    (net (code "83") (name "Net-(U3-V+)") (class "Default")
      (node (ref "C28") (pin "1") (pintype "passive"))
      (node (ref "U3") (pin "2") (pinfunction "V+_2") (pintype "passive"))
    )
    (net (code "84") (name "Net-(U3-V-)") (class "Default")
      (node (ref "C30") (pin "1") (pintype "passive"))
      (node (ref "U3") (pin "6") (pinfunction "V-_6") (pintype "passive"))
    )
    (net (code "85") (name "unconnected-(COM232-Pad1)") (class "Default")
      (node (ref "COM232") (pin "1") (pinfunction "1_1") (pintype "passive"))
    )
    (net (code "86") (name "unconnected-(COM232-Pad4)") (class "Default")
      (node (ref "COM232") (pin "4") (pinfunction "4_4") (pintype "passive"))
    )
    (net (code "87") (name "unconnected-(COM232-Pad6)") (class "Default")
      (node (ref "COM232") (pin "6") (pinfunction "6_6") (pintype "passive"))
    )
    (net (code "88") (name "unconnected-(COM232-Pad7)") (class "Default")
      (node (ref "COM232") (pin "7") (pinfunction "7_7") (pintype "passive"))
    )
    (net (code "89") (name "unconnected-(COM232-Pad8)") (class "Default")
      (node (ref "COM232") (pin "8") (pinfunction "8_8") (pintype "passive"))
    )
    (net (code "90") (name "unconnected-(COM232-Pad9)") (class "Default")
      (node (ref "COM232") (pin "9") (pinfunction "9_9") (pintype "passive"))
    )
    (net (code "91") (name "unconnected-(U1-PA8{slash}MCO1{slash}TIM1_CH1{slash}I2C3_SCL{slash}U1_CK{slash}OTG_FS_SOF{slash}LCD_R6-Pad119)") (class "Default")
      (node (ref "U1") (pin "119") (pinfunction "PA8/MCO1/TIM1_CH1/I2C3_SCL/U1_CK/OTG_FS_SOF/LCD_R6_119") (pintype "passive"))
    )
    (net (code "92") (name "unconnected-(U1-PA15{slash}JTDI{slash}TIM2_CH1{slash}TIM2_ETR{slash}SPI1_NSS{slash}SPI3_NSS{slash}I2S3_WS-Pad138)") (class "Default")
      (node (ref "U1") (pin "138") (pinfunction "PA15/JTDI/TIM2_CH1/TIM2_ETR/SPI1_NSS/SPI3_NSS/I2S3_WS_138") (pintype "passive"))
    )
    (net (code "93") (name "unconnected-(U1-PB0{slash}TIM1_CH2N{slash}TIM3_CH3{slash}TIM8_CH2N{slash}LCD_R3{slash}OTG_HS_ULPI_D1{slash}ETH_MII_RXD2{slash}ADC12_IN8-Pad56)") (class "Default")
      (node (ref "U1") (pin "56") (pinfunction "PB0/TIM1_CH2N/TIM3_CH3/TIM8_CH2N/LCD_R3/OTG_HS_ULPI_D1/ETH_MII_RXD2/ADC12_IN8_56") (pintype "passive"))
    )
    (net (code "94") (name "unconnected-(U1-PB3{slash}JTDO{slash}TIM2_CH2{slash}SPI1_SCK{slash}SPI3_SCK{slash}I2S3_CK-Pad161)") (class "Default")
      (node (ref "U1") (pin "161") (pinfunction "PB3/JTDO/TIM2_CH2/SPI1_SCK/SPI3_SCK/I2S3_CK_161") (pintype "passive"))
    )
    (net (code "95") (name "unconnected-(U1-PB8{slash}TIM4_CH3{slash}TIM10_CH1{slash}I2C1_SCL{slash}CAN1_RX{slash}ETH_MII_TXD3{slash}SDIO_D4{slash}DCMI_D6{slash}LCD_B6-Pad167)") (class "Default")
      (node (ref "U1") (pin "167") (pinfunction "PB8/TIM4_CH3/TIM10_CH1/I2C1_SCL/CAN1_RX/ETH_MII_TXD3/SDIO_D4/DCMI_D6/LCD_B6_167") (pintype "passive"))
    )
    (net (code "96") (name "unconnected-(U1-PB9{slash}TIM4_CH4{slash}TIM11_CH1{slash}I2C1_SDA{slash}SPI2_NSS{slash}I2S2_WS{slash}CAN1_TX{slash}SDIO_D5{slash}DCMI_D7{slash}LCD_B7-Pad168)") (class "Default")
      (node (ref "U1") (pin "168") (pinfunction "PB9/TIM4_CH4/TIM11_CH1/I2C1_SDA/SPI2_NSS/I2S2_WS/CAN1_TX/SDIO_D5/DCMI_D7/LCD_B7_168") (pintype "passive"))
    )
    (net (code "97") (name "unconnected-(U1-PB14{slash}TIM1_CH2N{slash}TIM8_CH2N{slash}SPI2_MISO{slash}I2S2ext_SD{slash}U3_RTS{slash}TIM12_CH1{slash}OTG_HS_DM-Pad94)") (class "Default")
      (node (ref "U1") (pin "94") (pinfunction "PB14/TIM1_CH2N/TIM8_CH2N/SPI2_MISO/I2S2ext_SD/U3_RTS/TIM12_CH1/OTG_HS_DM_94") (pintype "passive"))
    )
    (net (code "98") (name "unconnected-(U1-PB15{slash}RTC_REFIN{slash}TIM1_CH3N{slash}TIM8_CH3N{slash}SPI2_MOSI{slash}I2S2_SD{slash}TIM12_CH2{slash}OTG_HS_DP-Pad95)") (class "Default")
      (node (ref "U1") (pin "95") (pinfunction "PB15/RTC_REFIN/TIM1_CH3N/TIM8_CH3N/SPI2_MOSI/I2S2_SD/TIM12_CH2/OTG_HS_DP_95") (pintype "passive"))
    )
    (net (code "99") (name "unconnected-(U1-PC4{slash}ETH_MII_RXD0{slash}ETH_RMII_RXD0{slash}ADC12_IN14-Pad54)") (class "Default")
      (node (ref "U1") (pin "54") (pinfunction "PC4/ETH_MII_RXD0/ETH_RMII_RXD0/ADC12_IN14_54") (pintype "passive"))
    )
    (net (code "100") (name "unconnected-(U1-PC5{slash}ETH_MII_RXD1{slash}ETH_RMII_RXD1{slash}ADC12_IN15-Pad55)") (class "Default")
      (node (ref "U1") (pin "55") (pinfunction "PC5/ETH_MII_RXD1/ETH_RMII_RXD1/ADC12_IN15_55") (pintype "passive"))
    )
    (net (code "101") (name "unconnected-(U1-PC14{slash}OSC32_IN-Pad9)") (class "Default")
      (node (ref "U1") (pin "9") (pinfunction "PC14/OSC32_IN_9") (pintype "passive"))
    )
    (net (code "102") (name "unconnected-(U1-PC15{slash}OSC32_OUT-Pad10)") (class "Default")
      (node (ref "U1") (pin "10") (pinfunction "PC15/OSC32_OUT_10") (pintype "passive"))
    )
    (net (code "103") (name "unconnected-(U1-PD0{slash}CAN1_RX{slash}FMC_D2-Pad142)") (class "Default")
      (node (ref "U1") (pin "142") (pinfunction "PD0/CAN1_RX/FMC_D2_142") (pintype "passive"))
    )
    (net (code "104") (name "unconnected-(U1-PD1{slash}CAN1_TX{slash}FMC_D3-Pad143)") (class "Default")
      (node (ref "U1") (pin "143") (pinfunction "PD1/CAN1_TX/FMC_D3_143") (pintype "passive"))
    )
    (net (code "105") (name "unconnected-(U1-PD2{slash}TIM3_ETR{slash}U5_RX{slash}SDIO_CMD{slash}DCMI_D11-Pad144)") (class "Default")
      (node (ref "U1") (pin "144") (pinfunction "PD2/TIM3_ETR/U5_RX/SDIO_CMD/DCMI_D11_144") (pintype "passive"))
    )
    (net (code "106") (name "unconnected-(U1-PD3{slash}SPI2_SCK{slash}I2S2_CK{slash}U2_CTS{slash}FMC_CLK{slash}DCMI_D5{slash}LCD_G7-Pad145)") (class "Default")
      (node (ref "U1") (pin "145") (pinfunction "PD3/SPI2_SCK/I2S2_CK/U2_CTS/FMC_CLK/DCMI_D5/LCD_G7_145") (pintype "passive"))
    )
    (net (code "107") (name "unconnected-(U1-PD4{slash}U2_RTS{slash}FMC_NOE-Pad146)") (class "Default")
      (node (ref "U1") (pin "146") (pinfunction "PD4/U2_RTS/FMC_NOE_146") (pintype "passive"))
    )
    (net (code "108") (name "unconnected-(U1-PD5{slash}U2_TX{slash}FMC_NWE-Pad147)") (class "Default")
      (node (ref "U1") (pin "147") (pinfunction "PD5/U2_TX/FMC_NWE_147") (pintype "passive"))
    )
    (net (code "109") (name "unconnected-(U1-PD6{slash}SPI3_MOSI{slash}I2S3_SD{slash}SAI1_SD_A{slash}U2_RX{slash}FMC_NWAIT{slash}DCMI_D10{slash}LCD_B2-Pad150)") (class "Default")
      (node (ref "U1") (pin "150") (pinfunction "PD6/SPI3_MOSI/I2S3_SD/SAI1_SD_A/U2_RX/FMC_NWAIT/DCMI_D10/LCD_B2_150") (pintype "passive"))
    )
    (net (code "110") (name "unconnected-(U1-PD7{slash}U2_CK{slash}FMC_NE1{slash}FMC_NCE2-Pad151)") (class "Default")
      (node (ref "U1") (pin "151") (pinfunction "PD7/U2_CK/FMC_NE1/FMC_NCE2_151") (pintype "passive"))
    )
    (net (code "111") (name "unconnected-(U1-PD8{slash}U3_TX{slash}FMC_D13-Pad96)") (class "Default")
      (node (ref "U1") (pin "96") (pinfunction "PD8/U3_TX/FMC_D13_96") (pintype "passive"))
    )
    (net (code "112") (name "unconnected-(U1-PD9{slash}U3_RX{slash}FMC_D14-Pad97)") (class "Default")
      (node (ref "U1") (pin "97") (pinfunction "PD9/U3_RX/FMC_D14_97") (pintype "passive"))
    )
    (net (code "113") (name "unconnected-(U1-PD10{slash}U3_CK{slash}FMC_D15{slash}LCD_B3-Pad98)") (class "Default")
      (node (ref "U1") (pin "98") (pinfunction "PD10/U3_CK/FMC_D15/LCD_B3_98") (pintype "passive"))
    )
    (net (code "114") (name "unconnected-(U1-PD11{slash}U3_CTS{slash}FMC_A16-Pad99)") (class "Default")
      (node (ref "U1") (pin "99") (pinfunction "PD11/U3_CTS/FMC_A16_99") (pintype "passive"))
    )
    (net (code "115") (name "unconnected-(U1-PD12{slash}TIM4_CH1{slash}U3_RTS{slash}FMC_A17-Pad100)") (class "Default")
      (node (ref "U1") (pin "100") (pinfunction "PD12/TIM4_CH1/U3_RTS/FMC_A17_100") (pintype "passive"))
    )
    (net (code "116") (name "unconnected-(U1-PD13{slash}TIM4_CH2{slash}FMC_A18-Pad101)") (class "Default")
      (node (ref "U1") (pin "101") (pinfunction "PD13/TIM4_CH2/FMC_A18_101") (pintype "passive"))
    )
    (net (code "117") (name "unconnected-(U1-PE2{slash}SPI4_SCK{slash}SAI1_MCLK_A{slash}ETH_MII_TXD3{slash}FMC_A23-Pad1)") (class "Default")
      (node (ref "U1") (pin "1") (pinfunction "PE2/SPI4_SCK/SAI1_MCLK_A/ETH_MII_TXD3/FMC_A23_1") (pintype "passive"))
    )
    (net (code "118") (name "unconnected-(U1-PE3{slash}SAI1_SD_B{slash}FMC_A19-Pad2)") (class "Default")
      (node (ref "U1") (pin "2") (pinfunction "PE3/SAI1_SD_B/FMC_A19_2") (pintype "passive"))
    )
    (net (code "119") (name "unconnected-(U1-PE4{slash}SPI4_NSS{slash}SAI1_FS_A{slash}FMC_A20{slash}DCMI_D4{slash}LCD_B0-Pad3)") (class "Default")
      (node (ref "U1") (pin "3") (pinfunction "PE4/SPI4_NSS/SAI1_FS_A/FMC_A20/DCMI_D4/LCD_B0_3") (pintype "passive"))
    )
    (net (code "120") (name "unconnected-(U1-PE5{slash}TIM9_CH1{slash}SPI4_MISO{slash}SAI1_SCK_A{slash}FMC_A21{slash}DCMI_D6{slash}LCD_G0-Pad4)") (class "Default")
      (node (ref "U1") (pin "4") (pinfunction "PE5/TIM9_CH1/SPI4_MISO/SAI1_SCK_A/FMC_A21/DCMI_D6/LCD_G0_4") (pintype "passive"))
    )
    (net (code "121") (name "unconnected-(U1-PE6{slash}TIM9_CH2{slash}SPI4_MOSI{slash}SAI1_SD_A{slash}FMC_A22{slash}DCMI_D7{slash}LCD_G1-Pad5)") (class "Default")
      (node (ref "U1") (pin "5") (pinfunction "PE6/TIM9_CH2/SPI4_MOSI/SAI1_SD_A/FMC_A22/DCMI_D7/LCD_G1_5") (pintype "passive"))
    )
    (net (code "122") (name "unconnected-(U1-PE7{slash}TIM1_ETR{slash}U7_RX{slash}FMC_D4-Pad68)") (class "Default")
      (node (ref "U1") (pin "68") (pinfunction "PE7/TIM1_ETR/U7_RX/FMC_D4_68") (pintype "passive"))
    )
    (net (code "123") (name "unconnected-(U1-PE8{slash}TIM1_CH1N{slash}U7_TX{slash}FMC_D5-Pad69)") (class "Default")
      (node (ref "U1") (pin "69") (pinfunction "PE8/TIM1_CH1N/U7_TX/FMC_D5_69") (pintype "passive"))
    )
    (net (code "124") (name "unconnected-(U1-PE9{slash}TIM1_CH1{slash}FMC_D6-Pad70)") (class "Default")
      (node (ref "U1") (pin "70") (pinfunction "PE9/TIM1_CH1/FMC_D6_70") (pintype "passive"))
    )
    (net (code "125") (name "unconnected-(U1-PE10{slash}TIM1_CH2N{slash}FMC_D7-Pad73)") (class "Default")
      (node (ref "U1") (pin "73") (pinfunction "PE10/TIM1_CH2N/FMC_D7_73") (pintype "passive"))
    )
    (net (code "126") (name "unconnected-(U1-PE11{slash}TIM1_CH2{slash}SPI4_NSS{slash}FMC_D8{slash}LCD_G3-Pad74)") (class "Default")
      (node (ref "U1") (pin "74") (pinfunction "PE11/TIM1_CH2/SPI4_NSS/FMC_D8/LCD_G3_74") (pintype "passive"))
    )
    (net (code "127") (name "unconnected-(U1-PE12{slash}TIM1_CH3N{slash}SPI4_SCK{slash}FMC_D9{slash}LCD_B4-Pad75)") (class "Default")
      (node (ref "U1") (pin "75") (pinfunction "PE12/TIM1_CH3N/SPI4_SCK/FMC_D9/LCD_B4_75") (pintype "passive"))
    )
    (net (code "128") (name "unconnected-(U1-PE13{slash}TIM1_CH3{slash}SPI4_MISO{slash}FMC_D10{slash}LCD_DE-Pad76)") (class "Default")
      (node (ref "U1") (pin "76") (pinfunction "PE13/TIM1_CH3/SPI4_MISO/FMC_D10/LCD_DE_76") (pintype "passive"))
    )
    (net (code "129") (name "unconnected-(U1-PF0{slash}I2C2_SDA{slash}FMC_A0-Pad16)") (class "Default")
      (node (ref "U1") (pin "16") (pinfunction "PF0/I2C2_SDA/FMC_A0_16") (pintype "passive"))
    )
    (net (code "130") (name "unconnected-(U1-PF1{slash}I2C2_SCL{slash}FMC_A1-Pad17)") (class "Default")
      (node (ref "U1") (pin "17") (pinfunction "PF1/I2C2_SCL/FMC_A1_17") (pintype "passive"))
    )
    (net (code "131") (name "unconnected-(U1-PF2{slash}I2C2_SMBA{slash}FMC_A2-Pad18)") (class "Default")
      (node (ref "U1") (pin "18") (pinfunction "PF2/I2C2_SMBA/FMC_A2_18") (pintype "passive"))
    )
    (net (code "132") (name "unconnected-(U1-PF3{slash}FMC_A3{slash}ADC3_IN9-Pad19)") (class "Default")
      (node (ref "U1") (pin "19") (pinfunction "PF3/FMC_A3/ADC3_IN9_19") (pintype "passive"))
    )
    (net (code "133") (name "unconnected-(U1-PF4{slash}FMC_A4{slash}ADC3_IN14-Pad20)") (class "Default")
      (node (ref "U1") (pin "20") (pinfunction "PF4/FMC_A4/ADC3_IN14_20") (pintype "passive"))
    )
    (net (code "134") (name "unconnected-(U1-PF5{slash}FMC_A5{slash}ADC3_IN15-Pad21)") (class "Default")
      (node (ref "U1") (pin "21") (pinfunction "PF5/FMC_A5/ADC3_IN15_21") (pintype "passive"))
    )
    (net (code "135") (name "unconnected-(U1-PF10{slash}FMC_INTR{slash}DCMI_D11{slash}LCD_DE{slash}ADC3_IN8-Pad28)") (class "Default")
      (node (ref "U1") (pin "28") (pinfunction "PF10/FMC_INTR/DCMI_D11/LCD_DE/ADC3_IN8_28") (pintype "passive"))
    )
    (net (code "136") (name "unconnected-(U1-PF11{slash}SPI5_MOSI{slash}FMC_SDNRAS{slash}DCMI_D12-Pad59)") (class "Default")
      (node (ref "U1") (pin "59") (pinfunction "PF11/SPI5_MOSI/FMC_SDNRAS/DCMI_D12_59") (pintype "passive"))
    )
    (net (code "137") (name "unconnected-(U1-PF12{slash}FMC_A6-Pad60)") (class "Default")
      (node (ref "U1") (pin "60") (pinfunction "PF12/FMC_A6_60") (pintype "passive"))
    )
    (net (code "138") (name "unconnected-(U1-PF13{slash}FMC_A7-Pad63)") (class "Default")
      (node (ref "U1") (pin "63") (pinfunction "PF13/FMC_A7_63") (pintype "passive"))
    )
    (net (code "139") (name "unconnected-(U1-PF14{slash}FMC_A8-Pad64)") (class "Default")
      (node (ref "U1") (pin "64") (pinfunction "PF14/FMC_A8_64") (pintype "passive"))
    )
    (net (code "140") (name "unconnected-(U1-PF15{slash}FMC_A9-Pad65)") (class "Default")
      (node (ref "U1") (pin "65") (pinfunction "PF15/FMC_A9_65") (pintype "passive"))
    )
    (net (code "141") (name "unconnected-(U1-PG2{slash}FMC_A12-Pad106)") (class "Default")
      (node (ref "U1") (pin "106") (pinfunction "PG2/FMC_A12_106") (pintype "passive"))
    )
    (net (code "142") (name "unconnected-(U1-PG3{slash}FMC_A13-Pad107)") (class "Default")
      (node (ref "U1") (pin "107") (pinfunction "PG3/FMC_A13_107") (pintype "passive"))
    )
    (net (code "143") (name "unconnected-(U1-PG4{slash}FMC_A14{slash}FMC_BA0-Pad108)") (class "Default")
      (node (ref "U1") (pin "108") (pinfunction "PG4/FMC_A14/FMC_BA0_108") (pintype "passive"))
    )
    (net (code "144") (name "unconnected-(U1-PG5{slash}FMC_A15{slash}FMC_BA1-Pad109)") (class "Default")
      (node (ref "U1") (pin "109") (pinfunction "PG5/FMC_A15/FMC_BA1_109") (pintype "passive"))
    )
    (net (code "145") (name "unconnected-(U1-PG6{slash}FMC_INT2{slash}DCMI_D12{slash}LCD_R7-Pad110)") (class "Default")
      (node (ref "U1") (pin "110") (pinfunction "PG6/FMC_INT2/DCMI_D12/LCD_R7_110") (pintype "passive"))
    )
    (net (code "146") (name "unconnected-(U1-PG7{slash}U6_CK{slash}FMC_INT3{slash}DCMI_D13{slash}LCD_CLK-Pad111)") (class "Default")
      (node (ref "U1") (pin "111") (pinfunction "PG7/U6_CK/FMC_INT3/DCMI_D13/LCD_CLK_111") (pintype "passive"))
    )
    (net (code "147") (name "unconnected-(U1-PG8{slash}SPI6_NSS{slash}U6_RTS{slash}ETH_PPS_OUT{slash}FMC_SDCLK-Pad112)") (class "Default")
      (node (ref "U1") (pin "112") (pinfunction "PG8/SPI6_NSS/U6_RTS/ETH_PPS_OUT/FMC_SDCLK_112") (pintype "passive"))
    )
    (net (code "148") (name "unconnected-(U1-PG9{slash}U6_RX{slash}FMC_NE2{slash}FMC_NCE3-Pad152)") (class "Default")
      (node (ref "U1") (pin "152") (pinfunction "PG9/U6_RX/FMC_NE2/FMC_NCE3_152") (pintype "passive"))
    )
    (net (code "149") (name "unconnected-(U1-PG10{slash}LCD_G3{slash}FMC_NE3{slash}FMC_NCE4_1{slash}DCMI_D2{slash}LCD_B2-Pad153)") (class "Default")
      (node (ref "U1") (pin "153") (pinfunction "PG10/LCD_G3/FMC_NE3/FMC_NCE4_1/DCMI_D2/LCD_B2_153") (pintype "passive"))
    )
    (net (code "150") (name "unconnected-(U1-PG11{slash}ETH_MII_TX_EN{slash}ETH_RMII_TX_EN{slash}FMC_NCE4_2{slash}DCMI_D3{slash}LCD_B3-Pad154)") (class "Default")
      (node (ref "U1") (pin "154") (pinfunction "PG11/ETH_MII_TX_EN/ETH_RMII_TX_EN/FMC_NCE4_2/DCMI_D3/LCD_B3_154") (pintype "passive"))
    )
    (net (code "151") (name "unconnected-(U1-PG12{slash}SPI6_MISO{slash}U6_RTS{slash}FMC_NE4{slash}LCD_B1{slash}LCD_B4-Pad155)") (class "Default")
      (node (ref "U1") (pin "155") (pinfunction "PG12/SPI6_MISO/U6_RTS/FMC_NE4/LCD_B1/LCD_B4_155") (pintype "passive"))
    )
    (net (code "152") (name "unconnected-(U1-PG13{slash}SPI6_SCK{slash}U6_CTS{slash}ETH_MII_TXD0{slash}ETH_RMII_TXD0{slash}FMC_A24-Pad156)") (class "Default")
      (node (ref "U1") (pin "156") (pinfunction "PG13/SPI6_SCK/U6_CTS/ETH_MII_TXD0/ETH_RMII_TXD0/FMC_A24_156") (pintype "passive"))
    )
    (net (code "153") (name "unconnected-(U1-PG14{slash}SPI6_MOSI{slash}U6_TX{slash}ETH_MII_TXD1{slash}ETH_RMII_TXD1{slash}FMC_A25-Pad157)") (class "Default")
      (node (ref "U1") (pin "157") (pinfunction "PG14/SPI6_MOSI/U6_TX/ETH_MII_TXD1/ETH_RMII_TXD1/FMC_A25_157") (pintype "passive"))
    )
    (net (code "154") (name "unconnected-(U1-PG15{slash}U6_CTS{slash}FMC_SDNCAS{slash}DCMI_D13-Pad160)") (class "Default")
      (node (ref "U1") (pin "160") (pinfunction "PG15/U6_CTS/FMC_SDNCAS/DCMI_D13_160") (pintype "passive"))
    )
    (net (code "155") (name "unconnected-(U1-PH2{slash}ETH_MII_CRS{slash}FMC_SDCKE0{slash}LCD_R0-Pad43)") (class "Default")
      (node (ref "U1") (pin "43") (pinfunction "PH2/ETH_MII_CRS/FMC_SDCKE0/LCD_R0_43") (pintype "passive"))
    )
    (net (code "156") (name "unconnected-(U1-PH3{slash}ETH_MII_COL{slash}FMC_SDNE0{slash}LCD_R1-Pad44)") (class "Default")
      (node (ref "U1") (pin "44") (pinfunction "PH3/ETH_MII_COL/FMC_SDNE0/LCD_R1_44") (pintype "passive"))
    )
    (net (code "157") (name "unconnected-(U1-PH12{slash}TIM5_CH3{slash}FMC_D20{slash}DCMI_D3{slash}LCD_R6-Pad89)") (class "Default")
      (node (ref "U1") (pin "89") (pinfunction "PH12/TIM5_CH3/FMC_D20/DCMI_D3/LCD_R6_89") (pintype "passive"))
    )
    (net (code "158") (name "unconnected-(U1-PH13{slash}TIM8_CH1N{slash}CAN1_TX{slash}FMC_D21{slash}LCD_G2-Pad128)") (class "Default")
      (node (ref "U1") (pin "128") (pinfunction "PH13/TIM8_CH1N/CAN1_TX/FMC_D21/LCD_G2_128") (pintype "passive"))
    )
    (net (code "159") (name "unconnected-(U1-PH14{slash}TIM8_CH2N{slash}FMC_D22{slash}DCMI_D4{slash}LCD_G3-Pad129)") (class "Default")
      (node (ref "U1") (pin "129") (pinfunction "PH14/TIM8_CH2N/FMC_D22/DCMI_D4/LCD_G3_129") (pintype "passive"))
    )
    (net (code "160") (name "unconnected-(U1-PH15{slash}TIM8_CH3N{slash}FMC_D23{slash}DCMI_D11{slash}LCD_G4-Pad130)") (class "Default")
      (node (ref "U1") (pin "130") (pinfunction "PH15/TIM8_CH3N/FMC_D23/DCMI_D11/LCD_G4_130") (pintype "passive"))
    )
    (net (code "161") (name "unconnected-(U1-PI0{slash}TIM5_CH4{slash}SPI2_NSS{slash}I2S2_WS{slash}FMC_D24{slash}DCMI_D13{slash}LCD_G5-Pad131)") (class "Default")
      (node (ref "U1") (pin "131") (pinfunction "PI0/TIM5_CH4/SPI2_NSS/I2S2_WS/FMC_D24/DCMI_D13/LCD_G5_131") (pintype "passive"))
    )
    (net (code "162") (name "unconnected-(U1-PI1{slash}SPI2_SCK{slash}I2S2_CK{slash}FMC_D25{slash}DCMI_D8{slash}LCD_G6-Pad132)") (class "Default")
      (node (ref "U1") (pin "132") (pinfunction "PI1/SPI2_SCK/I2S2_CK/FMC_D25/DCMI_D8/LCD_G6_132") (pintype "passive"))
    )
    (net (code "163") (name "unconnected-(U1-PI2{slash}TIM8_CH4{slash}SPI2_MISO{slash}I2S2ext_SD{slash}FMC_D26{slash}DCMI_D9{slash}LCD_G7-Pad133)") (class "Default")
      (node (ref "U1") (pin "133") (pinfunction "PI2/TIM8_CH4/SPI2_MISO/I2S2ext_SD/FMC_D26/DCMI_D9/LCD_G7_133") (pintype "passive"))
    )
    (net (code "164") (name "unconnected-(U1-PI3{slash}TIM8_ETR{slash}SPI2_MOSI{slash}I2S2_SD{slash}FMC_D27{slash}DCMI_D10-Pad134)") (class "Default")
      (node (ref "U1") (pin "134") (pinfunction "PI3/TIM8_ETR/SPI2_MOSI/I2S2_SD/FMC_D27/DCMI_D10_134") (pintype "passive"))
    )
    (net (code "165") (name "unconnected-(U1-PI8{slash}TAMP_2-Pad7)") (class "Default")
      (node (ref "U1") (pin "7") (pinfunction "PI8/TAMP_2_7") (pintype "passive"))
    )
    (net (code "166") (name "unconnected-(U1-PI9{slash}CAN1_RX{slash}FMC_D30{slash}LCD_VSYNC-Pad11)") (class "Default")
      (node (ref "U1") (pin "11") (pinfunction "PI9/CAN1_RX/FMC_D30/LCD_VSYNC_11") (pintype "passive"))
    )
    (net (code "167") (name "unconnected-(U1-PI10{slash}ETH_MII_RX_ER{slash}FMC_D31{slash}LCD_HSYNC-Pad12)") (class "Default")
      (node (ref "U1") (pin "12") (pinfunction "PI10/ETH_MII_RX_ER/FMC_D31/LCD_HSYNC_12") (pintype "passive"))
    )
    (net (code "168") (name "unconnected-(U1-PI11{slash}OTG_HS_ULPI_DIR-Pad13)") (class "Default")
      (node (ref "U1") (pin "13") (pinfunction "PI11/OTG_HS_ULPI_DIR_13") (pintype "passive"))
    )
    (net (code "169") (name "unconnected-(U3-DIN2-Pad10)") (class "Default")
      (node (ref "U3") (pin "10") (pinfunction "DIN2_10") (pintype "passive"))
    )
    (net (code "170") (name "unconnected-(U3-DOUT2-Pad7)") (class "Default")
      (node (ref "U3") (pin "7") (pinfunction "DOUT2_7") (pintype "passive"))
    )
    (net (code "171") (name "unconnected-(U3-RIN2-Pad8)") (class "Default")
      (node (ref "U3") (pin "8") (pinfunction "RIN2_8") (pintype "passive"))
    )
    (net (code "172") (name "unconnected-(U3-ROUT2-Pad9)") (class "Default")
      (node (ref "U3") (pin "9") (pinfunction "ROUT2_9") (pintype "passive"))
    )
  )
)
